# MCU.net
KiCad netlist of a schematic drawn in Altium Designer
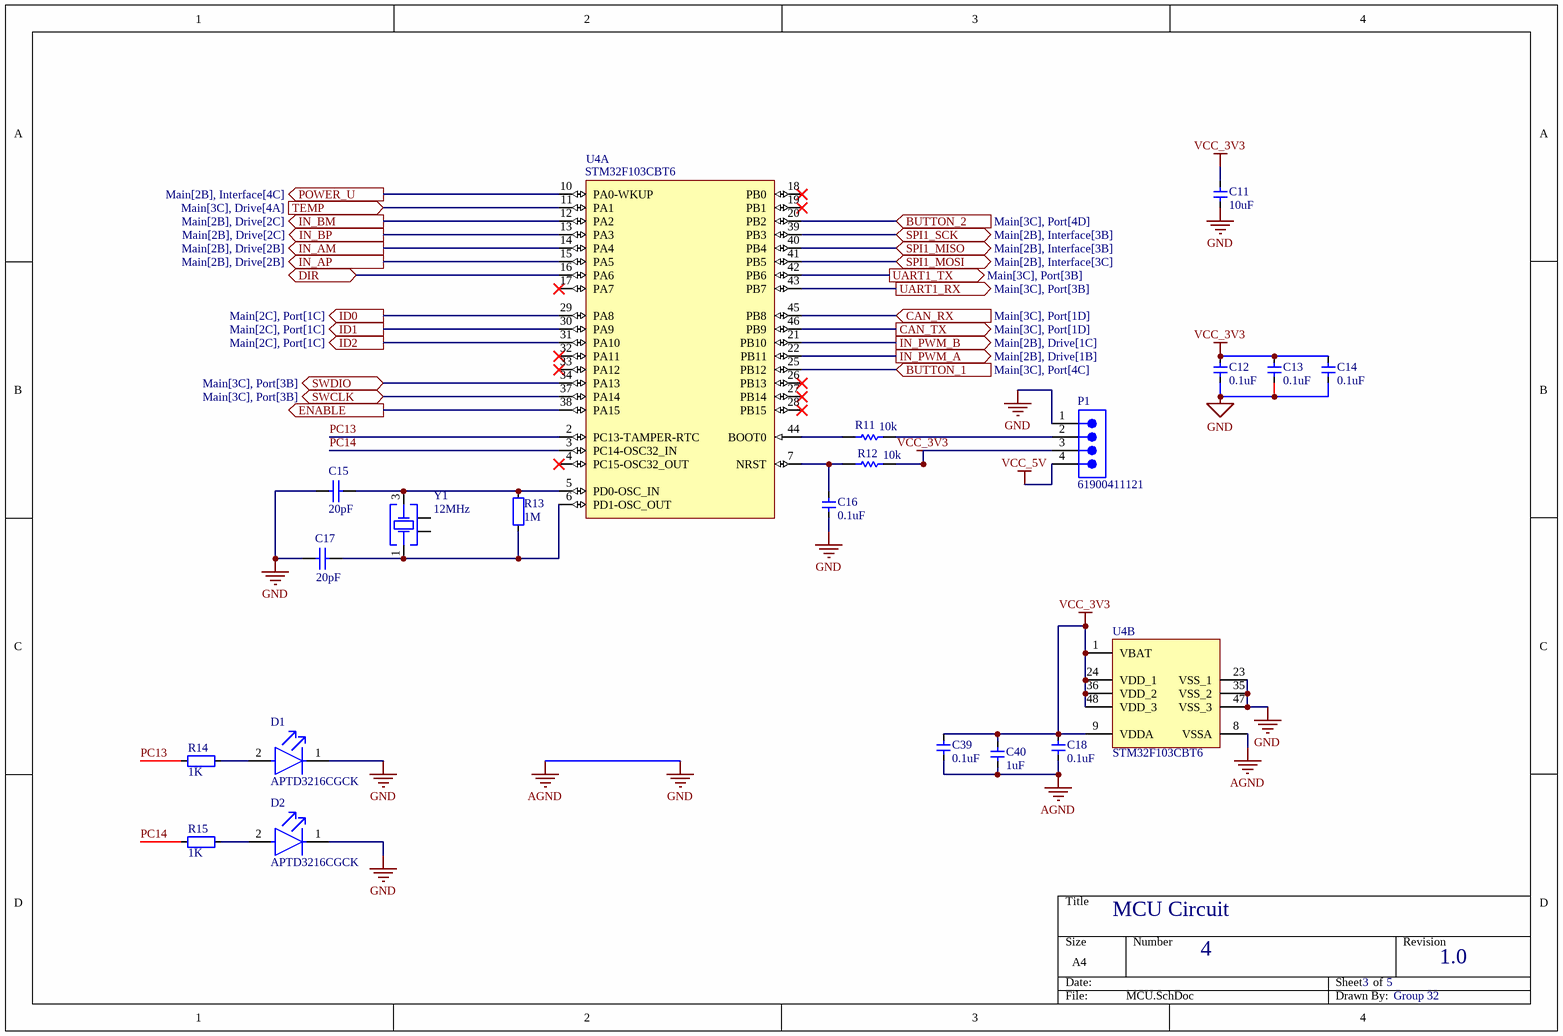
[diagram p0: MCU.SchDoc]

(export (version "E")
  (design (tool "Eeschema 10.0.6"))
  (components
    (comp (ref "C11")
      (value "10uF")
      (footprint "CAPC2013X94X50LL20T25")
      (description "Capacitor")
      (libsource (lib "MyPcbLib") (part "电容-0402"))
    )
    (comp (ref "C12")
      (value "0.1uF")
      (footprint "CAPC2013X94X50LL20T25")
      (description "Capacitor")
      (libsource (lib "MyPcbLib") (part "电容-0402"))
    )
    (comp (ref "C13")
      (value "0.1uF")
      (footprint "CAPC2013X94X50LL20T25")
      (description "Capacitor")
      (libsource (lib "MyPcbLib") (part "电容-0402"))
    )
    (comp (ref "C14")
      (value "0.1uF")
      (footprint "CAPC2013X94X50LL20T25")
      (description "Capacitor")
      (libsource (lib "MyPcbLib") (part "电容-0402"))
    )
    (comp (ref "C15")
      (value "08055A200JAT2A")
      (footprint "CAPC2013X94X50LL20T25")
      (fields (field (name "MANUFACTURER") "AVX Interconnect / Elco") (field (name "RESISTANCE") "20pF"))
      (libsource (lib "Altium Content Vault") (part "CAP"))
    )
    (comp (ref "C16")
      (value "0.1uF")
      (footprint "CAPC2013X94X50LL20T25")
      (description "Capacitor")
      (libsource (lib "MyPcbLib") (part "电容-0402"))
    )
    (comp (ref "C17")
      (value "08055A200JAT2A")
      (footprint "CAPC2013X94X50LL20T25")
      (fields (field (name "MANUFACTURER") "AVX Interconnect / Elco") (field (name "RESISTANCE") "20pF"))
      (libsource (lib "Altium Content Vault") (part "CAP"))
    )
    (comp (ref "C18")
      (value "0.1uF")
      (footprint "CAPC2013X94X50LL20T25")
      (description "Capacitor")
      (libsource (lib "MyPcbLib") (part "电容-0402"))
    )
    (comp (ref "C39")
      (value "0.1uF")
      (footprint "CAPC2013X94X50LL20T25")
      (description "Capacitor")
      (libsource (lib "MyPcbLib") (part "电容-0402"))
    )
    (comp (ref "C40")
      (value "1uF")
      (footprint "CAPC2013X94X50LL20T25")
      (description "Capacitor")
      (libsource (lib "MyPcbLib") (part "电容-0402"))
    )
    (comp (ref "D1")
      (value "APTD3216CGCK")
      (footprint "FP-APTD3216CGCK-MFG")
      (description "LED GREEN CLEAR 2SMD")
      (libsource (lib "Altium Content Vault") (part "8706943c75ba83719d021d2fdc84c58"))
    )
    (comp (ref "D2")
      (value "APTD3216CGCK")
      (footprint "FP-APTD3216CGCK-MFG")
      (description "LED GREEN CLEAR 2SMD")
      (libsource (lib "Altium Content Vault") (part "8706943c75ba83719d021d2fdc84c58"))
    )
    (comp (ref "P1")
      (value "61900411121")
      (footprint "61900411121")
      (libsource (lib "Altium Content Vault") (part "Header_Male_1R_04P"))
    )
    (comp (ref "R11")
      (value "RC0805FR-0710KL")
      (footprint "RESC2013X60X35NL10T20")
      (description "Chip Resistor, 10 KOhm, +/- 1%, 0.125 W, -55 to 155 degC, 0805 (2012 Metric), RoHS, Tape and Reel")
      (fields (field (name "MANUFACTURER") "Yageo") (field (name "RES") "10k"))
      (libsource (lib "Altium Content Vault") (part "RES-2"))
    )
    (comp (ref "R12")
      (value "RC0805FR-0710KL")
      (footprint "RESC2013X60X35NL10T20")
      (description "Chip Resistor, 10 KOhm, +/- 1%, 0.125 W, -55 to 155 degC, 0805 (2012 Metric), RoHS, Tape and Reel")
      (fields (field (name "MANUFACTURER") "Yageo") (field (name "RES") "10k"))
      (libsource (lib "Altium Content Vault") (part "RES-2"))
    )
    (comp (ref "R13")
      (value "1M")
      (footprint "RESC2013X60X35NL10T20")
      (description "Resistor")
      (libsource (lib "") (part "电阻-0402_1"))
    )
    (comp (ref "R14")
      (value "1K")
      (footprint "RESC3116X65N")
      (description "Resistor")
      (libsource (lib "MyPcbLib") (part "电阻-0402"))
    )
    (comp (ref "R15")
      (value "1K")
      (footprint "RESC3116X65N")
      (description "Resistor")
      (libsource (lib "MyPcbLib") (part "电阻-0402"))
    )
    (comp (ref "U4")
      (value "STM32F103CBT6")
      (footprint "STM-LQFP48_L")
      (libsource (lib "Altium Content Vault") (part "MC-ARM-STM32F103X8_B-SQ48"))
    )
    (comp (ref "Y1")
      (value "830069944")
      (footprint "WE-XTAL_CFPX-180")
      (description "830069944 WE-XTAL Quartz Crystal")
      (fields (field (name "FREQUENCY") "12MHz"))
      (libsource (lib "Altium Content Vault") (part "WE-XTAL_CFPX-180"))
    )
  )
  (nets
    (net (code "1") (name "/BUTTON_1") (class "Default")
      (node (ref "U4") (pin "25") (pinfunction "PB12_25") (pintype "bidirectional"))
    )
    (net (code "2") (name "/BUTTON_2") (class "Default")
      (node (ref "U4") (pin "20") (pinfunction "PB2_20") (pintype "bidirectional"))
    )
    (net (code "3") (name "/CAN_RX") (class "Default")
      (node (ref "U4") (pin "45") (pinfunction "PB8_45") (pintype "bidirectional"))
    )
    (net (code "4") (name "/CAN_TX") (class "Default")
      (node (ref "U4") (pin "46") (pinfunction "PB9_46") (pintype "bidirectional"))
    )
    (net (code "5") (name "/DIR") (class "Default")
      (node (ref "U4") (pin "16") (pinfunction "PA6_16") (pintype "bidirectional"))
    )
    (net (code "6") (name "/ENABLE") (class "Default")
      (node (ref "U4") (pin "38") (pinfunction "PA15_38") (pintype "bidirectional"))
    )
    (net (code "7") (name "/ID0") (class "Default")
      (node (ref "U4") (pin "29") (pinfunction "PA8_29") (pintype "bidirectional"))
    )
    (net (code "8") (name "/ID1") (class "Default")
      (node (ref "U4") (pin "30") (pinfunction "PA9_30") (pintype "bidirectional"))
    )
    (net (code "9") (name "/ID2") (class "Default")
      (node (ref "U4") (pin "31") (pinfunction "PA10_31") (pintype "bidirectional"))
    )
    (net (code "10") (name "/IN_AM") (class "Default")
      (node (ref "U4") (pin "14") (pinfunction "PA4_14") (pintype "bidirectional"))
    )
    (net (code "11") (name "/IN_AP") (class "Default")
      (node (ref "U4") (pin "15") (pinfunction "PA5_15") (pintype "bidirectional"))
    )
    (net (code "12") (name "/IN_BM") (class "Default")
      (node (ref "U4") (pin "12") (pinfunction "PA2_12") (pintype "bidirectional"))
    )
    (net (code "13") (name "/IN_BP") (class "Default")
      (node (ref "U4") (pin "13") (pinfunction "PA3_13") (pintype "bidirectional"))
    )
    (net (code "14") (name "/IN_PWM_A") (class "Default")
      (node (ref "U4") (pin "22") (pinfunction "PB11_22") (pintype "bidirectional"))
    )
    (net (code "15") (name "/IN_PWM_B") (class "Default")
      (node (ref "U4") (pin "21") (pinfunction "PB10_21") (pintype "bidirectional"))
    )
    (net (code "16") (name "/PC13") (class "Default")
      (node (ref "R14") (pin "1") (pinfunction "1_1") (pintype "passive"))
      (node (ref "U4") (pin "2") (pinfunction "PC13-TAMPER-RTC_2") (pintype "bidirectional"))
    )
    (net (code "17") (name "/PC14") (class "Default")
      (node (ref "R15") (pin "1") (pinfunction "1_1") (pintype "passive"))
      (node (ref "U4") (pin "3") (pinfunction "PC14-OSC32_IN_3") (pintype "bidirectional"))
    )
    (net (code "18") (name "/POWER_U") (class "Default")
      (node (ref "U4") (pin "10") (pinfunction "PA0-WKUP_10") (pintype "bidirectional"))
    )
    (net (code "19") (name "/SPI1_MISO") (class "Default")
      (node (ref "U4") (pin "40") (pinfunction "PB4_40") (pintype "bidirectional"))
    )
    (net (code "20") (name "/SPI1_MOSI") (class "Default")
      (node (ref "U4") (pin "41") (pinfunction "PB5_41") (pintype "bidirectional"))
    )
    (net (code "21") (name "/SPI1_SCK") (class "Default")
      (node (ref "U4") (pin "39") (pinfunction "PB3_39") (pintype "bidirectional"))
    )
    (net (code "22") (name "/SWCLK") (class "Default")
      (node (ref "U4") (pin "37") (pinfunction "PA14_37") (pintype "bidirectional"))
    )
    (net (code "23") (name "/SWDIO") (class "Default")
      (node (ref "U4") (pin "34") (pinfunction "PA13_34") (pintype "bidirectional"))
    )
    (net (code "24") (name "/TEMP") (class "Default")
      (node (ref "U4") (pin "11") (pinfunction "PA1_11") (pintype "bidirectional"))
    )
    (net (code "25") (name "/UART1_RX") (class "Default")
      (node (ref "U4") (pin "43") (pinfunction "PB7_43") (pintype "bidirectional"))
    )
    (net (code "26") (name "/UART1_TX") (class "Default")
      (node (ref "U4") (pin "42") (pinfunction "PB6_42") (pintype "bidirectional"))
    )
    (net (code "27") (name "AGND") (class "Default")
      (node (ref "C11") (pin "1") (pinfunction "1_1") (pintype "passive"))
      (node (ref "C12") (pin "1") (pinfunction "1_1") (pintype "passive"))
      (node (ref "C13") (pin "1") (pinfunction "1_1") (pintype "passive"))
      (node (ref "C14") (pin "1") (pinfunction "1_1") (pintype "passive"))
      (node (ref "C15") (pin "1") (pinfunction "1_1") (pintype "passive"))
      (node (ref "C16") (pin "1") (pinfunction "1_1") (pintype "passive"))
      (node (ref "C17") (pin "1") (pinfunction "1_1") (pintype "passive"))
      (node (ref "C18") (pin "1") (pinfunction "1_1") (pintype "passive"))
      (node (ref "C39") (pin "1") (pinfunction "1_1") (pintype "passive"))
      (node (ref "C40") (pin "1") (pinfunction "1_1") (pintype "passive"))
      (node (ref "D1") (pin "1") (pinfunction "C_1") (pintype "passive"))
      (node (ref "D2") (pin "1") (pinfunction "C_1") (pintype "passive"))
      (node (ref "P1") (pin "1") (pinfunction "1_1") (pintype "passive"))
      (node (ref "U4") (pin "23") (pinfunction "VSS_1_23") (pintype "power_in"))
      (node (ref "U4") (pin "35") (pinfunction "VSS_2_35") (pintype "power_in"))
      (node (ref "U4") (pin "47") (pinfunction "VSS_3_47") (pintype "power_in"))
      (node (ref "U4") (pin "8") (pinfunction "VSSA_8") (pintype "power_in"))
    )
    (net (code "28") (name "Net-(D1-A)") (class "Default")
      (node (ref "D1") (pin "2") (pinfunction "A_2") (pintype "passive"))
      (node (ref "R14") (pin "2") (pinfunction "2_2") (pintype "passive"))
    )
    (net (code "29") (name "Net-(D2-A)") (class "Default")
      (node (ref "D2") (pin "2") (pinfunction "A_2") (pintype "passive"))
      (node (ref "R15") (pin "2") (pinfunction "2_2") (pintype "passive"))
    )
    (net (code "30") (name "Net-(P1-Pad2)") (class "Default")
      (node (ref "P1") (pin "2") (pinfunction "2_2") (pintype "passive"))
      (node (ref "R11") (pin "2") (pinfunction "2_2") (pintype "passive"))
    )
    (net (code "31") (name "Net-(U4A-BOOT0)") (class "Default")
      (node (ref "R11") (pin "1") (pinfunction "1_1") (pintype "passive"))
      (node (ref "U4") (pin "44") (pinfunction "BOOT0_44") (pintype "input"))
    )
    (net (code "32") (name "Net-(U4A-NRST)") (class "Default")
      (node (ref "C16") (pin "2") (pinfunction "2_2") (pintype "passive"))
      (node (ref "R12") (pin "1") (pinfunction "1_1") (pintype "passive"))
      (node (ref "U4") (pin "7") (pinfunction "NRST_7") (pintype "bidirectional"))
    )
    (net (code "33") (name "Net-(U4A-PD0-OSC_IN)") (class "Default")
      (node (ref "C15") (pin "2") (pinfunction "2_2") (pintype "passive"))
      (node (ref "R13") (pin "2") (pinfunction "2_2") (pintype "passive"))
      (node (ref "U4") (pin "5") (pinfunction "PD0-OSC_IN_5") (pintype "bidirectional"))
      (node (ref "Y1") (pin "3") (pinfunction "Crystal_3") (pintype "passive"))
    )
    (net (code "34") (name "Net-(U4A-PD1-OSC_OUT)") (class "Default")
      (node (ref "C17") (pin "2") (pinfunction "2_2") (pintype "passive"))
      (node (ref "R13") (pin "1") (pinfunction "1_1") (pintype "passive"))
      (node (ref "U4") (pin "6") (pinfunction "PD1-OSC_OUT_6") (pintype "bidirectional"))
      (node (ref "Y1") (pin "1") (pinfunction "Crystal_1") (pintype "passive"))
    )
    (net (code "35") (name "VCC_3V3") (class "Default")
      (node (ref "C11") (pin "2") (pinfunction "2_2") (pintype "passive"))
      (node (ref "C12") (pin "2") (pinfunction "2_2") (pintype "passive"))
      (node (ref "C13") (pin "2") (pinfunction "2_2") (pintype "passive"))
      (node (ref "C14") (pin "2") (pinfunction "2_2") (pintype "passive"))
      (node (ref "C18") (pin "2") (pinfunction "2_2") (pintype "passive"))
      (node (ref "C39") (pin "2") (pinfunction "2_2") (pintype "passive"))
      (node (ref "C40") (pin "2") (pinfunction "2_2") (pintype "passive"))
      (node (ref "P1") (pin "3") (pinfunction "3_3") (pintype "passive"))
      (node (ref "R12") (pin "2") (pinfunction "2_2") (pintype "passive"))
      (node (ref "U4") (pin "1") (pinfunction "VBAT_1") (pintype "power_in"))
      (node (ref "U4") (pin "24") (pinfunction "VDD_1_24") (pintype "power_in"))
      (node (ref "U4") (pin "36") (pinfunction "VDD_2_36") (pintype "power_in"))
      (node (ref "U4") (pin "48") (pinfunction "VDD_3_48") (pintype "power_in"))
      (node (ref "U4") (pin "9") (pinfunction "VDDA_9") (pintype "power_in"))
    )
    (net (code "36") (name "VCC_5V") (class "Default")
      (node (ref "P1") (pin "4") (pinfunction "4_4") (pintype "passive"))
    )
    (net (code "37") (name "unconnected-(U4A-PA7-Pad17)") (class "Default")
      (node (ref "U4") (pin "17") (pinfunction "PA7_17") (pintype "bidirectional+no_connect"))
    )
    (net (code "38") (name "unconnected-(U4A-PA11-Pad32)") (class "Default")
      (node (ref "U4") (pin "32") (pinfunction "PA11_32") (pintype "bidirectional+no_connect"))
    )
    (net (code "39") (name "unconnected-(U4A-PA12-Pad33)") (class "Default")
      (node (ref "U4") (pin "33") (pinfunction "PA12_33") (pintype "bidirectional+no_connect"))
    )
    (net (code "40") (name "unconnected-(U4A-PB0-Pad18)") (class "Default")
      (node (ref "U4") (pin "18") (pinfunction "PB0_18") (pintype "bidirectional+no_connect"))
    )
    (net (code "41") (name "unconnected-(U4A-PB1-Pad19)") (class "Default")
      (node (ref "U4") (pin "19") (pinfunction "PB1_19") (pintype "bidirectional+no_connect"))
    )
    (net (code "42") (name "unconnected-(U4A-PB13-Pad26)") (class "Default")
      (node (ref "U4") (pin "26") (pinfunction "PB13_26") (pintype "bidirectional+no_connect"))
    )
    (net (code "43") (name "unconnected-(U4A-PB14-Pad27)") (class "Default")
      (node (ref "U4") (pin "27") (pinfunction "PB14_27") (pintype "bidirectional+no_connect"))
    )
    (net (code "44") (name "unconnected-(U4A-PB15-Pad28)") (class "Default")
      (node (ref "U4") (pin "28") (pinfunction "PB15_28") (pintype "bidirectional+no_connect"))
    )
    (net (code "45") (name "unconnected-(U4A-PC15-OSC32_OUT-Pad4)") (class "Default")
      (node (ref "U4") (pin "4") (pinfunction "PC15-OSC32_OUT_4") (pintype "bidirectional+no_connect"))
    )
    (net (code "46") (name "unconnected-(Y1-GND&Lid-Pad2)") (class "Default")
      (node (ref "Y1") (pin "2") (pinfunction "GND&Lid_2") (pintype "passive"))
    )
    (net (code "47") (name "unconnected-(Y1-GND&Lid-Pad4)") (class "Default")
      (node (ref "Y1") (pin "4") (pinfunction "GND&Lid_4") (pintype "passive"))
    )
  )
)
